# Sheet3-key.net
KiCad netlist of a schematic drawn in Altium Designer
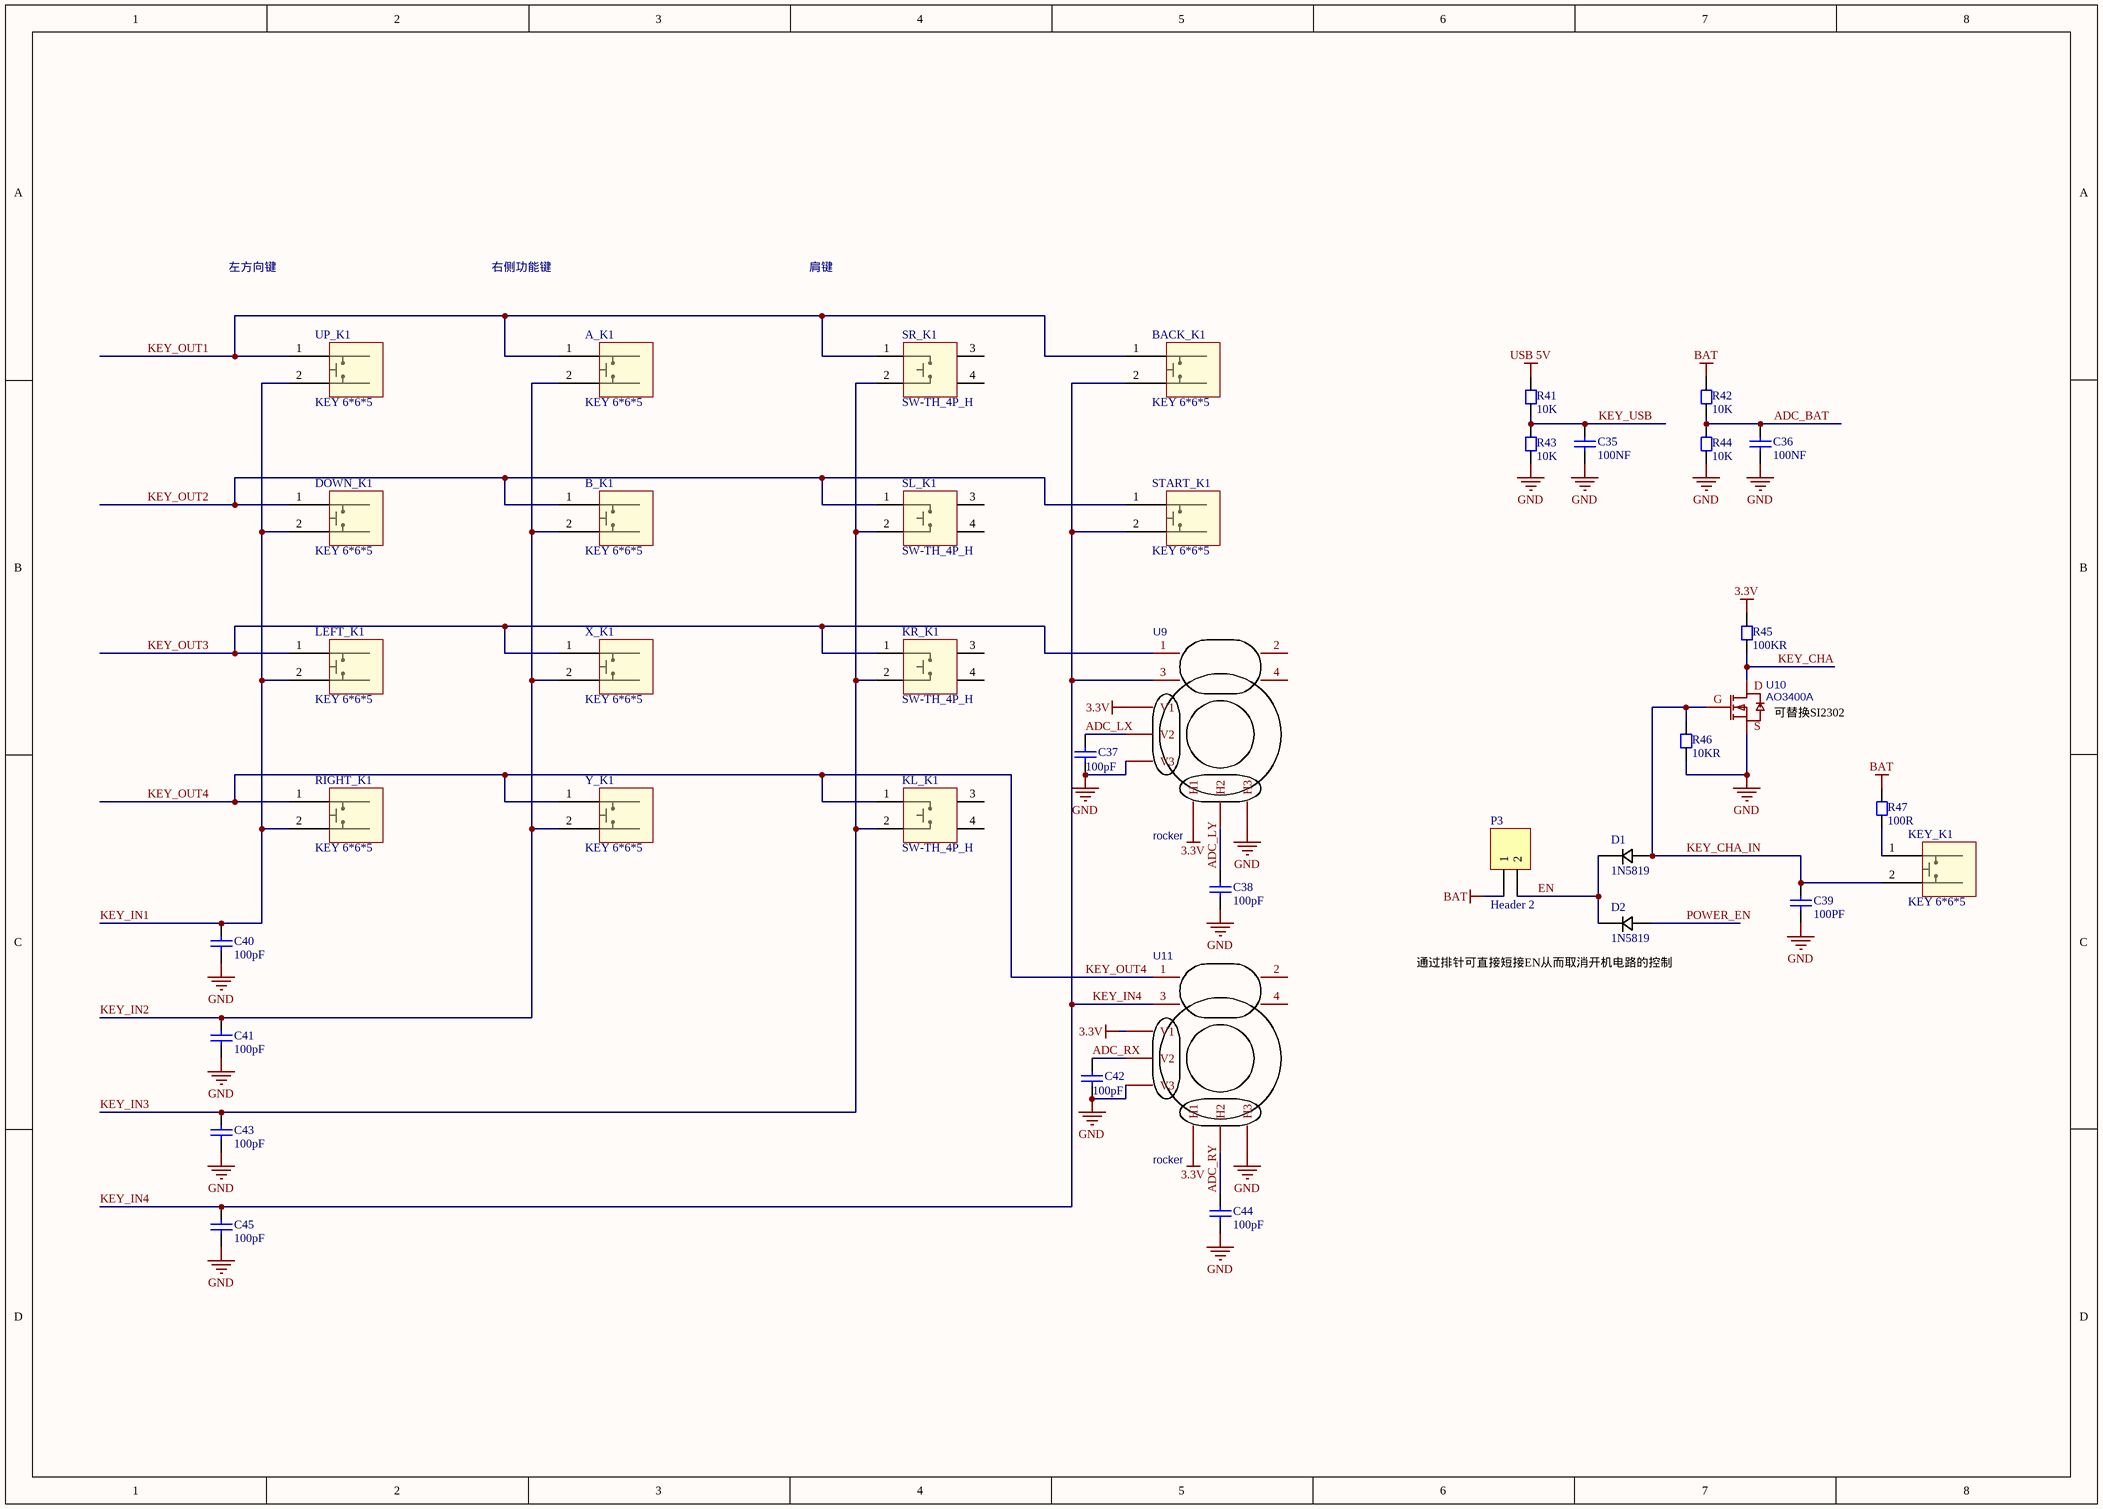
[diagram p0: Sheet3-key.SchDoc]

(export (version "E")
  (design (tool "Eeschema 10.0.6"))
  (components
    (comp (ref "A_K1")
      (value "KEY 6*6*5")
      (footprint "KEY 6*6*5")
      (description "无声轻触开关")
      (libsource (lib "base") (part "KEY 6*6*5"))
    )
    (comp (ref "BACK_K1")
      (value "KEY 6*6*5")
      (footprint "KEY 6*6*5")
      (description "无声轻触开关")
      (libsource (lib "base") (part "KEY 6*6*5"))
    )
    (comp (ref "B_K1")
      (value "KEY 6*6*5")
      (footprint "KEY 6*6*5")
      (description "无声轻触开关")
      (libsource (lib "base") (part "KEY 6*6*5"))
    )
    (comp (ref "C35")
      (value "100NF")
      (footprint "CC1608-0603")
      (description "0603封装的电容")
      (fields (field (name "PUBLISHER") "Altium Limited"))
      (libsource (lib "base") (part "Cap Chip 0603"))
    )
    (comp (ref "C36")
      (value "100NF")
      (footprint "CC1608-0603")
      (description "0603封装的电容")
      (fields (field (name "PUBLISHER") "Altium Limited"))
      (libsource (lib "base") (part "Cap Chip 0603"))
    )
    (comp (ref "C37")
      (value "100pF")
      (footprint "CC1608-0603")
      (description "0603封装的电容")
      (fields (field (name "PUBLISHER") "Altium Limited"))
      (libsource (lib "base") (part "Cap Chip 0603"))
    )
    (comp (ref "C38")
      (value "100pF")
      (footprint "CC1608-0603")
      (description "0603封装的电容")
      (fields (field (name "PUBLISHER") "Altium Limited"))
      (libsource (lib "base") (part "Cap Chip 0603"))
    )
    (comp (ref "C39")
      (value "100PF")
      (footprint "CC1608-0603")
      (description "0603封装的电容")
      (fields (field (name "PUBLISHER") "Altium Limited"))
      (libsource (lib "base") (part "Cap Chip 0603"))
    )
    (comp (ref "C40")
      (value "100pF")
      (footprint "CC1608-0603")
      (description "0603封装的电容")
      (fields (field (name "PUBLISHER") "Altium Limited"))
      (libsource (lib "base") (part "Cap Chip 0603"))
    )
    (comp (ref "C41")
      (value "100pF")
      (footprint "CC1608-0603")
      (description "0603封装的电容")
      (fields (field (name "PUBLISHER") "Altium Limited"))
      (libsource (lib "base") (part "Cap Chip 0603"))
    )
    (comp (ref "C42")
      (value "100pF")
      (footprint "CC1608-0603")
      (description "0603封装的电容")
      (fields (field (name "PUBLISHER") "Altium Limited"))
      (libsource (lib "base") (part "Cap Chip 0603"))
    )
    (comp (ref "C43")
      (value "100pF")
      (footprint "CC1608-0603")
      (description "0603封装的电容")
      (fields (field (name "PUBLISHER") "Altium Limited"))
      (libsource (lib "base") (part "Cap Chip 0603"))
    )
    (comp (ref "C44")
      (value "100pF")
      (footprint "CC1608-0603")
      (description "0603封装的电容")
      (fields (field (name "PUBLISHER") "Altium Limited"))
      (libsource (lib "base") (part "Cap Chip 0603"))
    )
    (comp (ref "C45")
      (value "100pF")
      (footprint "CC1608-0603")
      (description "0603封装的电容")
      (fields (field (name "PUBLISHER") "Altium Limited"))
      (libsource (lib "base") (part "Cap Chip 0603"))
    )
    (comp (ref "D1")
      (value "1N5819")
      (footprint "SOD-323_L1.8-W1.3-LS2.5-RD")
      (description "肖特基二极管")
      (libsource (lib "transistor") (part "1N5819"))
    )
    (comp (ref "D2")
      (value "1N5819")
      (footprint "SOD-323_L1.8-W1.3-LS2.5-RD")
      (description "肖特基二极管")
      (libsource (lib "transistor") (part "1N5819"))
    )
    (comp (ref "DOWN_K1")
      (value "KEY 6*6*5")
      (footprint "KEY 6*6*5")
      (description "无声轻触开关")
      (libsource (lib "base") (part "KEY 6*6*5"))
    )
    (comp (ref "KEY_K1")
      (value "KEY 6*6*5")
      (footprint "KEY 6*6*5")
      (description "无声轻触开关")
      (libsource (lib "base") (part "KEY 6*6*5"))
    )
    (comp (ref "KL_K1")
      (value "SW-TH_4P_H")
      (footprint "SW-TH_KH-6X6X7H-ZJ")
      (description "卧式轻触开关")
      (libsource (lib "base") (part "SW-TH_4P_H"))
    )
    (comp (ref "KR_K1")
      (value "SW-TH_4P_H")
      (footprint "SW-TH_KH-6X6X7H-ZJ")
      (description "卧式轻触开关")
      (libsource (lib "base") (part "SW-TH_4P_H"))
    )
    (comp (ref "LEFT_K1")
      (value "KEY 6*6*5")
      (footprint "KEY 6*6*5")
      (description "无声轻触开关")
      (libsource (lib "base") (part "KEY 6*6*5"))
    )
    (comp (ref "P3")
      (value "Header 2")
      (footprint "HDR1X2")
      (description "Header, 2-Pin")
      (fields (field (name "PUBLISHER") "Altium Limited"))
      (libsource (lib "Connectors") (part "Header 2"))
    )
    (comp (ref "R41")
      (value "10K")
      (footprint "CR1608-0603")
      (description "0603封装电阻")
      (fields (field (name "PUBLISHER") "Altium Limited"))
      (libsource (lib "") (part "Resistor Chip 0603_1"))
    )
    (comp (ref "R42")
      (value "10K")
      (footprint "CR1608-0603")
      (description "0603封装电阻")
      (fields (field (name "PUBLISHER") "Altium Limited"))
      (libsource (lib "") (part "Resistor Chip 0603_1"))
    )
    (comp (ref "R43")
      (value "10K")
      (footprint "CR1608-0603")
      (description "0603封装电阻")
      (fields (field (name "PUBLISHER") "Altium Limited"))
      (libsource (lib "") (part "Resistor Chip 0603_1"))
    )
    (comp (ref "R44")
      (value "10K")
      (footprint "CR1608-0603")
      (description "0603封装电阻")
      (fields (field (name "PUBLISHER") "Altium Limited"))
      (libsource (lib "") (part "Resistor Chip 0603_1"))
    )
    (comp (ref "R45")
      (value "100KR")
      (footprint "CR1608-0603")
      (description "贴片电阻")
      (libsource (lib "tianxiaohua_Schlib") (part "Chip resistor"))
    )
    (comp (ref "R46")
      (value "10KR")
      (footprint "CR1608-0603")
      (description "贴片电阻")
      (libsource (lib "tianxiaohua_Schlib") (part "Chip resistor"))
    )
    (comp (ref "R47")
      (value "100R")
      (footprint "CR1608-0603")
      (description "0603封装电阻")
      (fields (field (name "PUBLISHER") "Altium Limited"))
      (libsource (lib "base") (part "Resistor Chip 0603"))
    )
    (comp (ref "RIGHT_K1")
      (value "KEY 6*6*5")
      (footprint "KEY 6*6*5")
      (description "无声轻触开关")
      (libsource (lib "base") (part "KEY 6*6*5"))
    )
    (comp (ref "SL_K1")
      (value "SW-TH_4P_H")
      (footprint "SW-TH_KH-6X6X7H-ZJ")
      (description "卧式轻触开关")
      (libsource (lib "base") (part "SW-TH_4P_H"))
    )
    (comp (ref "SR_K1")
      (value "SW-TH_4P_H")
      (footprint "SW-TH_KH-6X6X7H-ZJ")
      (description "卧式轻触开关")
      (libsource (lib "base") (part "SW-TH_4P_H"))
    )
    (comp (ref "START_K1")
      (value "KEY 6*6*5")
      (footprint "KEY 6*6*5")
      (description "无声轻触开关")
      (libsource (lib "base") (part "KEY 6*6*5"))
    )
    (comp (ref "U9")
      (value "rocker")
      (footprint "PCBComponent_1")
      (fields (field (name "MANUFACTURER PART") "摇杆") (field (name "CONTRIBUTOR") "Alex_Ai"))
      (libsource (lib "base") (part "rocker"))
    )
    (comp (ref "U10")
      (value "AO3400A")
      (footprint "SOT-23")
      (description "UMW AO3400A SOT-23 30V/5.8A N沟道 MOS(场效应管)芯片")
      (fields
        (field (name "MANUFACTURER") "ElecSuper(静芯微）")
        (field (name "MANUFACTURER PART") "AO3401A")
        (field (name "CONTRIBUTOR") "lcsc")
      )
      (libsource (lib "transistor") (part "AO3400A"))
    )
    (comp (ref "U11")
      (value "rocker")
      (footprint "PCBComponent_1")
      (fields (field (name "MANUFACTURER PART") "摇杆") (field (name "CONTRIBUTOR") "Alex_Ai"))
      (libsource (lib "base") (part "rocker"))
    )
    (comp (ref "UP_K1")
      (value "KEY 6*6*5")
      (footprint "KEY 6*6*5")
      (description "无声轻触开关")
      (libsource (lib "base") (part "KEY 6*6*5"))
    )
    (comp (ref "X_K1")
      (value "KEY 6*6*5")
      (footprint "KEY 6*6*5")
      (description "无声轻触开关")
      (libsource (lib "base") (part "KEY 6*6*5"))
    )
    (comp (ref "Y_K1")
      (value "KEY 6*6*5")
      (footprint "KEY 6*6*5")
      (description "无声轻触开关")
      (libsource (lib "base") (part "KEY 6*6*5"))
    )
  )
  (nets
    (net (code "1") (name "/ADC_BAT") (class "Default")
      (node (ref "C36") (pin "2") (pinfunction "2_2") (pintype "passive"))
      (node (ref "R42") (pin "1") (pinfunction "1_1") (pintype "passive"))
      (node (ref "R44") (pin "2") (pinfunction "2_2") (pintype "passive"))
    )
    (net (code "2") (name "/ADC_LX") (class "Default")
      (node (ref "C37") (pin "2") (pinfunction "2_2") (pintype "passive"))
      (node (ref "U9") (pin "6") (pinfunction "V2_6") (pintype "passive"))
    )
    (net (code "3") (name "/ADC_LY") (class "Default")
      (node (ref "C38") (pin "2") (pinfunction "2_2") (pintype "passive"))
      (node (ref "U9") (pin "9") (pinfunction "H2_9") (pintype "passive"))
    )
    (net (code "4") (name "/ADC_RX") (class "Default")
      (node (ref "C42") (pin "2") (pinfunction "2_2") (pintype "passive"))
      (node (ref "U11") (pin "6") (pinfunction "V2_6") (pintype "passive"))
    )
    (net (code "5") (name "/ADC_RY") (class "Default")
      (node (ref "C44") (pin "2") (pinfunction "2_2") (pintype "passive"))
      (node (ref "U11") (pin "9") (pinfunction "H2_9") (pintype "passive"))
    )
    (net (code "6") (name "/EN") (class "Default")
      (node (ref "D1") (pin "1") (pinfunction "1_1") (pintype "passive"))
      (node (ref "D2") (pin "1") (pinfunction "1_1") (pintype "passive"))
      (node (ref "P3") (pin "2") (pinfunction "2_2") (pintype "passive"))
    )
    (net (code "7") (name "/KEY_CHA") (class "Default")
      (node (ref "R45") (pin "1") (pinfunction "1_1") (pintype "passive"))
      (node (ref "U10") (pin "3") (pinfunction "D_3") (pintype "passive"))
    )
    (net (code "8") (name "/KEY_CHA_IN") (class "Default")
      (node (ref "C39") (pin "1") (pinfunction "1_1") (pintype "passive"))
      (node (ref "D1") (pin "2") (pinfunction "2_2") (pintype "passive"))
      (node (ref "KEY_K1") (pin "2") (pinfunction "2_2") (pintype "passive"))
      (node (ref "R46") (pin "2") (pinfunction "2_2") (pintype "passive"))
      (node (ref "U10") (pin "1") (pinfunction "G_1") (pintype "passive"))
    )
    (net (code "9") (name "/KEY_IN1") (class "Default")
      (node (ref "C40") (pin "2") (pinfunction "2_2") (pintype "passive"))
      (node (ref "DOWN_K1") (pin "2") (pinfunction "2_2") (pintype "passive"))
      (node (ref "LEFT_K1") (pin "2") (pinfunction "2_2") (pintype "passive"))
      (node (ref "RIGHT_K1") (pin "2") (pinfunction "2_2") (pintype "passive"))
      (node (ref "UP_K1") (pin "2") (pinfunction "2_2") (pintype "passive"))
    )
    (net (code "10") (name "/KEY_IN2") (class "Default")
      (node (ref "A_K1") (pin "2") (pinfunction "2_2") (pintype "passive"))
      (node (ref "B_K1") (pin "2") (pinfunction "2_2") (pintype "passive"))
      (node (ref "C41") (pin "2") (pinfunction "2_2") (pintype "passive"))
      (node (ref "X_K1") (pin "2") (pinfunction "2_2") (pintype "passive"))
      (node (ref "Y_K1") (pin "2") (pinfunction "2_2") (pintype "passive"))
    )
    (net (code "11") (name "/KEY_IN3") (class "Default")
      (node (ref "C43") (pin "2") (pinfunction "2_2") (pintype "passive"))
      (node (ref "KL_K1") (pin "2") (pinfunction "2_2") (pintype "passive"))
      (node (ref "KR_K1") (pin "2") (pinfunction "2_2") (pintype "passive"))
      (node (ref "SL_K1") (pin "2") (pinfunction "2_2") (pintype "passive"))
      (node (ref "SR_K1") (pin "2") (pinfunction "2_2") (pintype "passive"))
    )
    (net (code "12") (name "/KEY_IN4") (class "Default")
      (node (ref "BACK_K1") (pin "2") (pinfunction "2_2") (pintype "passive"))
      (node (ref "C45") (pin "2") (pinfunction "2_2") (pintype "passive"))
      (node (ref "START_K1") (pin "2") (pinfunction "2_2") (pintype "passive"))
      (node (ref "U11") (pin "3") (pinfunction "3_3") (pintype "passive"))
      (node (ref "U9") (pin "3") (pinfunction "3_3") (pintype "passive"))
    )
    (net (code "13") (name "/KEY_OUT1") (class "Default")
      (node (ref "A_K1") (pin "1") (pinfunction "1_1") (pintype "passive"))
      (node (ref "BACK_K1") (pin "1") (pinfunction "1_1") (pintype "passive"))
      (node (ref "SR_K1") (pin "1") (pinfunction "1_1") (pintype "passive"))
      (node (ref "UP_K1") (pin "1") (pinfunction "1_1") (pintype "passive"))
    )
    (net (code "14") (name "/KEY_OUT2") (class "Default")
      (node (ref "B_K1") (pin "1") (pinfunction "1_1") (pintype "passive"))
      (node (ref "DOWN_K1") (pin "1") (pinfunction "1_1") (pintype "passive"))
      (node (ref "SL_K1") (pin "1") (pinfunction "1_1") (pintype "passive"))
      (node (ref "START_K1") (pin "1") (pinfunction "1_1") (pintype "passive"))
    )
    (net (code "15") (name "/KEY_OUT3") (class "Default")
      (node (ref "KR_K1") (pin "1") (pinfunction "1_1") (pintype "passive"))
      (node (ref "LEFT_K1") (pin "1") (pinfunction "1_1") (pintype "passive"))
      (node (ref "U9") (pin "1") (pinfunction "1_1") (pintype "passive"))
      (node (ref "X_K1") (pin "1") (pinfunction "1_1") (pintype "passive"))
    )
    (net (code "16") (name "/KEY_OUT4") (class "Default")
      (node (ref "KL_K1") (pin "1") (pinfunction "1_1") (pintype "passive"))
      (node (ref "RIGHT_K1") (pin "1") (pinfunction "1_1") (pintype "passive"))
      (node (ref "U11") (pin "1") (pinfunction "1_1") (pintype "passive"))
      (node (ref "Y_K1") (pin "1") (pinfunction "1_1") (pintype "passive"))
    )
    (net (code "17") (name "/KEY_USB") (class "Default")
      (node (ref "C35") (pin "2") (pinfunction "2_2") (pintype "passive"))
      (node (ref "R41") (pin "1") (pinfunction "1_1") (pintype "passive"))
      (node (ref "R43") (pin "2") (pinfunction "2_2") (pintype "passive"))
    )
    (net (code "18") (name "/POWER_EN") (class "Default")
      (node (ref "D2") (pin "2") (pinfunction "2_2") (pintype "passive"))
    )
    (net (code "19") (name "3.3V") (class "Default")
      (node (ref "R45") (pin "2") (pinfunction "2_2") (pintype "passive"))
      (node (ref "U11") (pin "5") (pinfunction "V1_5") (pintype "passive"))
      (node (ref "U11") (pin "8") (pinfunction "H1_8") (pintype "passive"))
      (node (ref "U9") (pin "5") (pinfunction "V1_5") (pintype "passive"))
      (node (ref "U9") (pin "8") (pinfunction "H1_8") (pintype "passive"))
    )
    (net (code "20") (name "BAT") (class "Default")
      (node (ref "P3") (pin "1") (pinfunction "1_1") (pintype "passive"))
      (node (ref "R42") (pin "2") (pinfunction "2_2") (pintype "passive"))
      (node (ref "R47") (pin "1") (pinfunction "1_1") (pintype "passive"))
    )
    (net (code "21") (name "GND") (class "Default")
      (node (ref "C35") (pin "1") (pinfunction "1_1") (pintype "passive"))
      (node (ref "C36") (pin "1") (pinfunction "1_1") (pintype "passive"))
      (node (ref "C37") (pin "1") (pinfunction "1_1") (pintype "passive"))
      (node (ref "C38") (pin "1") (pinfunction "1_1") (pintype "passive"))
      (node (ref "C39") (pin "2") (pinfunction "2_2") (pintype "passive"))
      (node (ref "C40") (pin "1") (pinfunction "1_1") (pintype "passive"))
      (node (ref "C41") (pin "1") (pinfunction "1_1") (pintype "passive"))
      (node (ref "C42") (pin "1") (pinfunction "1_1") (pintype "passive"))
      (node (ref "C43") (pin "1") (pinfunction "1_1") (pintype "passive"))
      (node (ref "C44") (pin "1") (pinfunction "1_1") (pintype "passive"))
      (node (ref "C45") (pin "1") (pinfunction "1_1") (pintype "passive"))
      (node (ref "R43") (pin "1") (pinfunction "1_1") (pintype "passive"))
      (node (ref "R44") (pin "1") (pinfunction "1_1") (pintype "passive"))
      (node (ref "R46") (pin "1") (pinfunction "1_1") (pintype "passive"))
      (node (ref "U10") (pin "2") (pinfunction "S_2") (pintype "passive"))
      (node (ref "U11") (pin "10") (pinfunction "H3_10") (pintype "passive"))
      (node (ref "U11") (pin "7") (pinfunction "V3_7") (pintype "passive"))
      (node (ref "U9") (pin "10") (pinfunction "H3_10") (pintype "passive"))
      (node (ref "U9") (pin "7") (pinfunction "V3_7") (pintype "passive"))
    )
    (net (code "22") (name "Net-(KEY_K1-Pad1)") (class "Default")
      (node (ref "KEY_K1") (pin "1") (pinfunction "1_1") (pintype "passive"))
      (node (ref "R47") (pin "2") (pinfunction "2_2") (pintype "passive"))
    )
    (net (code "23") (name "USB 5V") (class "Default")
      (node (ref "R41") (pin "2") (pinfunction "2_2") (pintype "passive"))
    )
    (net (code "24") (name "unconnected-(KL_K1-Pad3)") (class "Default")
      (node (ref "KL_K1") (pin "3") (pinfunction "3_3") (pintype "passive"))
    )
    (net (code "25") (name "unconnected-(KL_K1-Pad4)") (class "Default")
      (node (ref "KL_K1") (pin "4") (pinfunction "4_4") (pintype "passive"))
    )
    (net (code "26") (name "unconnected-(KR_K1-Pad3)") (class "Default")
      (node (ref "KR_K1") (pin "3") (pinfunction "3_3") (pintype "passive"))
    )
    (net (code "27") (name "unconnected-(KR_K1-Pad4)") (class "Default")
      (node (ref "KR_K1") (pin "4") (pinfunction "4_4") (pintype "passive"))
    )
    (net (code "28") (name "unconnected-(SL_K1-Pad3)") (class "Default")
      (node (ref "SL_K1") (pin "3") (pinfunction "3_3") (pintype "passive"))
    )
    (net (code "29") (name "unconnected-(SL_K1-Pad4)") (class "Default")
      (node (ref "SL_K1") (pin "4") (pinfunction "4_4") (pintype "passive"))
    )
    (net (code "30") (name "unconnected-(SR_K1-Pad3)") (class "Default")
      (node (ref "SR_K1") (pin "3") (pinfunction "3_3") (pintype "passive"))
    )
    (net (code "31") (name "unconnected-(SR_K1-Pad4)") (class "Default")
      (node (ref "SR_K1") (pin "4") (pinfunction "4_4") (pintype "passive"))
    )
    (net (code "32") (name "unconnected-(U9-Pad2)") (class "Default")
      (node (ref "U9") (pin "2") (pinfunction "2_2") (pintype "passive"))
    )
    (net (code "33") (name "unconnected-(U9-Pad4)") (class "Default")
      (node (ref "U9") (pin "4") (pinfunction "4_4") (pintype "passive"))
    )
    (net (code "34") (name "unconnected-(U11-Pad2)") (class "Default")
      (node (ref "U11") (pin "2") (pinfunction "2_2") (pintype "passive"))
    )
    (net (code "35") (name "unconnected-(U11-Pad4)") (class "Default")
      (node (ref "U11") (pin "4") (pinfunction "4_4") (pintype "passive"))
    )
  )
)
